# 1_Sheet_1.net
KiCad netlist of a schematic drawn in Altium Designer
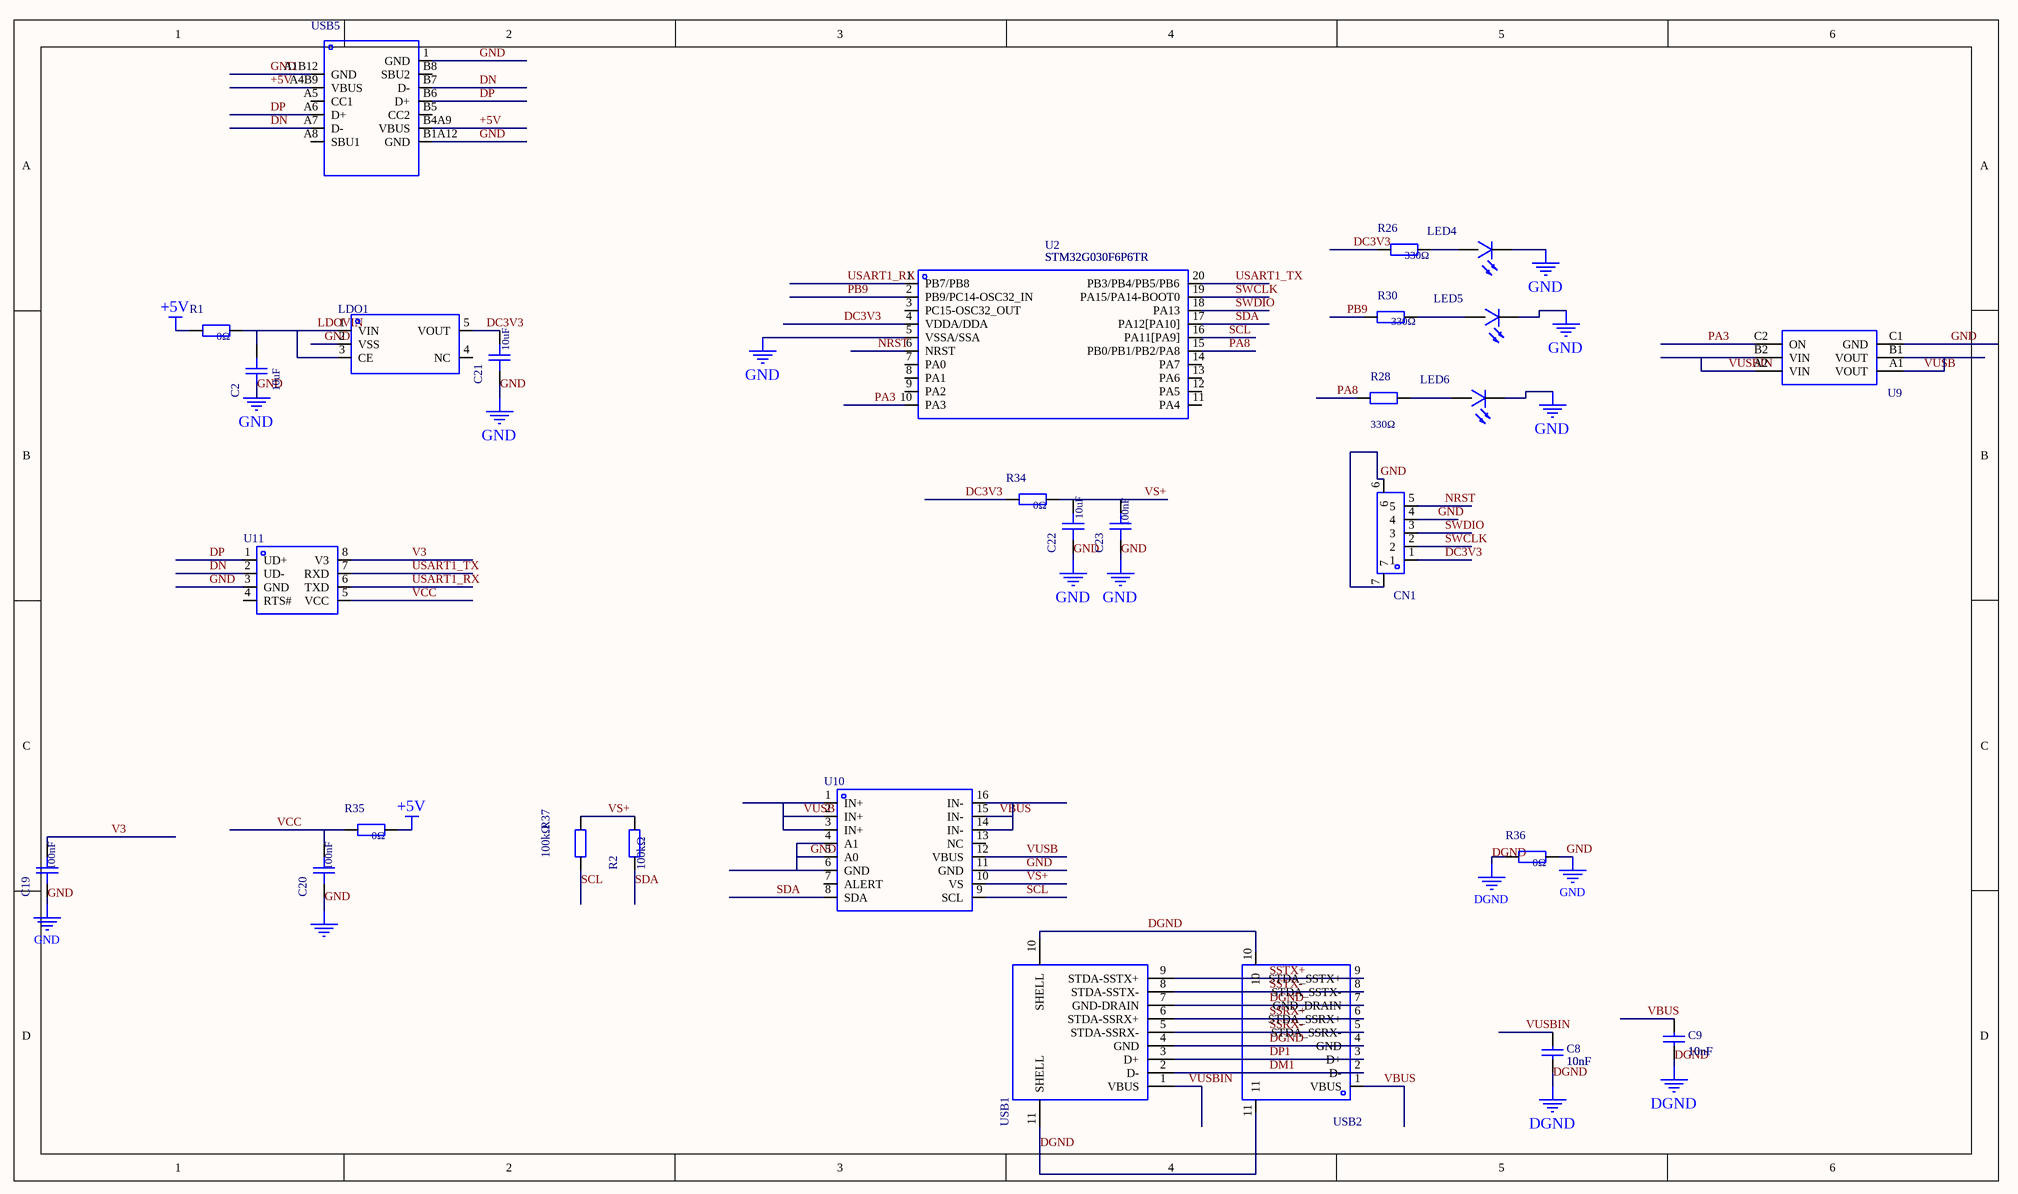
[diagram p0: 1_Sheet_1.schdoc]

(export (version "E")
  (design (tool "Eeschema 10.0.6"))
  (components
    (comp (ref "C2")
      (value "~")
      (fields
        (field (name "MANUFACTURER") "SAMSUNG(三星)")
        (field (name "MANUFACTURER PART") "CL10A106MA8NRNC")
        (field (name "TOLERANCE") "±20%")
        (field (name "CAPACITANCE") "10uF")
      )
      (libsource (lib "altium-import") (part "root_1_CL10A106MA8NRNC_"))
    )
    (comp (ref "C8")
      (value "10nF")
      (fields
        (field (name "NAME") "10nF")
        (field (name "MANUFACTURER PART") "CL05B103KB5NNNC")
        (field (name "MANUFACTURER") "SAMSUNG")
      )
      (libsource (lib "altium-import") (part "root_1_CL05B103KB5NNNC_"))
    )
    (comp (ref "C9")
      (value "10nF")
      (fields
        (field (name "NAME") "10nF")
        (field (name "MANUFACTURER PART") "CL05B103KB5NNNC")
        (field (name "MANUFACTURER") "SAMSUNG")
      )
      (libsource (lib "altium-import") (part "root_1_CL05B103KB5NNNC_"))
    )
    (comp (ref "C19")
      (value "~")
      (fields
        (field (name "MANUFACTURER") "YAGEO(国巨)")
        (field (name "MANUFACTURER PART") "CC0402KRX7R7BB104")
        (field (name "CAPACITANCE") "100nF")
        (field (name "TOLERANCE") "±10%")
      )
      (libsource (lib "altium-import") (part "root_1_CC0402KRX7R7BB104_"))
    )
    (comp (ref "C20")
      (value "~")
      (fields
        (field (name "MANUFACTURER") "YAGEO(国巨)")
        (field (name "MANUFACTURER PART") "CC0402KRX7R7BB104")
        (field (name "CAPACITANCE") "100nF")
        (field (name "TOLERANCE") "±10%")
      )
      (libsource (lib "altium-import") (part "root_1_CC0402KRX7R7BB104_"))
    )
    (comp (ref "C21")
      (value "~")
      (fields
        (field (name "MANUFACTURER") "SAMSUNG(三星)")
        (field (name "MANUFACTURER PART") "CL10A106MA8NRNC")
        (field (name "TOLERANCE") "±20%")
        (field (name "CAPACITANCE") "10uF")
      )
      (libsource (lib "altium-import") (part "root_1_CL10A106MA8NRNC_"))
    )
    (comp (ref "C22")
      (value "~")
      (fields
        (field (name "MANUFACTURER") "SAMSUNG(三星)")
        (field (name "MANUFACTURER PART") "CL10A106MA8NRNC")
        (field (name "TOLERANCE") "±20%")
        (field (name "CAPACITANCE") "10uF")
      )
      (libsource (lib "altium-import") (part "root_1_CL10A106MA8NRNC_"))
    )
    (comp (ref "C23")
      (value "~")
      (fields
        (field (name "MANUFACTURER") "YAGEO(国巨)")
        (field (name "MANUFACTURER PART") "CC0402KRX7R7BB104")
        (field (name "CAPACITANCE") "100nF")
        (field (name "TOLERANCE") "±10%")
      )
      (libsource (lib "altium-import") (part "root_1_CC0402KRX7R7BB104_"))
    )
    (comp (ref "CN1")
      (value "~")
      (fields (field (name "MANUFACTURER") "SHOU HAN(首韩)") (field (name "MANUFACTURER PART") "2.54-5P LT"))
      (libsource (lib "altium-import") (part "root_2_2.54-5P LT_"))
    )
    (comp (ref "LDO1")
      (value "~")
      (description "最大输入电压:6V;压降(max):260mV @ 200mA(typ);输出电压(可调):-;静态电流(Iq):-;输出类型:固定;输出电压(固定):3.3V;")
      (fields
        (field (name "MANUFACTURER") "MICRONE(南京微盟)")
        (field (name "MANUFACTURER PART") "ME6211C33M5G-N")
      )
      (libsource (lib "altium-import") (part "root_0_ME6211C33M5G-N_"))
    )
    (comp (ref "LED4")
      (value "~")
      (description "照明颜色:红色;")
      (fields
        (field (name "MANUFACTURER") "EVERLIGHT(台湾亿光)")
        (field (name "MANUFACTURER PART") "16-213/SDRC/S530-A3/TR8")
      )
      (libsource (lib "altium-import") (part "root_2_16-213/SDRC/S530-A3/TR8_"))
    )
    (comp (ref "LED5")
      (value "~")
      (description "照明颜色:红色;")
      (fields
        (field (name "MANUFACTURER") "EVERLIGHT(台湾亿光)")
        (field (name "MANUFACTURER PART") "16-213/SDRC/S530-A3/TR8")
      )
      (libsource (lib "altium-import") (part "root_2_16-213/SDRC/S530-A3/TR8_"))
    )
    (comp (ref "LED6")
      (value "~")
      (description "照明颜色:红色;")
      (fields
        (field (name "MANUFACTURER") "EVERLIGHT(台湾亿光)")
        (field (name "MANUFACTURER PART") "16-213/SDRC/S530-A3/TR8")
      )
      (libsource (lib "altium-import") (part "root_2_16-213/SDRC/S530-A3/TR8_"))
    )
    (comp (ref "R1")
      (value "~")
      (fields
        (field (name "MANUFACTURER") "YAGEO(国巨)")
        (field (name "MANUFACTURER PART") "RC0402FR-070RL")
        (field (name "TOLERANCE") "±1%")
        (field (name "RESISTANCE") "0Ω")
      )
      (libsource (lib "altium-import") (part "root_0_RC0402FR-070RL_"))
    )
    (comp (ref "R2")
      (value "100kΩ")
      (fields
        (field (name "MANUFACTURER") "FH(风华)")
        (field (name "MANUFACTURER PART") "RC-02W104JT")
        (field (name "TOLERANCE") "±5%")
      )
      (libsource (lib "altium-import") (part "root_1_RC-02W104JT_"))
    )
    (comp (ref "R26")
      (value "~")
      (fields
        (field (name "MANUFACTURER") "UNI-ROYAL(厚声)")
        (field (name "MANUFACTURER PART") "0402WGF3300TCE")
        (field (name "RESISTANCE") "330Ω")
        (field (name "TOLERANCE") "±1%")
      )
      (libsource (lib "altium-import") (part "root_0_0402WGF3300TCE_"))
    )
    (comp (ref "R28")
      (value "~")
      (fields
        (field (name "MANUFACTURER") "UNI-ROYAL(厚声)")
        (field (name "MANUFACTURER PART") "0402WGF3300TCE")
        (field (name "RESISTANCE") "330Ω")
        (field (name "TOLERANCE") "±1%")
      )
      (libsource (lib "altium-import") (part "root_0_0402WGF3300TCE_"))
    )
    (comp (ref "R30")
      (value "~")
      (fields
        (field (name "MANUFACTURER") "UNI-ROYAL(厚声)")
        (field (name "MANUFACTURER PART") "0402WGF3300TCE")
        (field (name "RESISTANCE") "330Ω")
        (field (name "TOLERANCE") "±1%")
      )
      (libsource (lib "altium-import") (part "root_0_0402WGF3300TCE_"))
    )
    (comp (ref "R34")
      (value "~")
      (fields
        (field (name "MANUFACTURER") "YAGEO(国巨)")
        (field (name "MANUFACTURER PART") "RC0402FR-070RL")
        (field (name "TOLERANCE") "±1%")
        (field (name "RESISTANCE") "0Ω")
      )
      (libsource (lib "altium-import") (part "root_0_RC0402FR-070RL_"))
    )
    (comp (ref "R35")
      (value "~")
      (fields
        (field (name "MANUFACTURER") "YAGEO(国巨)")
        (field (name "MANUFACTURER PART") "RC0402FR-070RL")
        (field (name "TOLERANCE") "±1%")
        (field (name "RESISTANCE") "0Ω")
      )
      (libsource (lib "altium-import") (part "root_0_RC0402FR-070RL_"))
    )
    (comp (ref "R36")
      (value "~")
      (fields
        (field (name "MANUFACTURER") "YAGEO(国巨)")
        (field (name "MANUFACTURER PART") "RC0402FR-070RL")
        (field (name "TOLERANCE") "±1%")
        (field (name "RESISTANCE") "0Ω")
      )
      (libsource (lib "altium-import") (part "root_0_RC0402FR-070RL_"))
    )
    (comp (ref "R37")
      (value "100kΩ")
      (fields
        (field (name "MANUFACTURER") "FH(风华)")
        (field (name "MANUFACTURER PART") "RC-02W104JT")
        (field (name "TOLERANCE") "±5%")
      )
      (libsource (lib "altium-import") (part "root_1_RC-02W104JT_"))
    )
    (comp (ref "U2")
      (value "STM32G030F6P6TR")
      (fields (field (name "NAME") "STM32G030F6P6TR") (field (name "MANUFACTURER") "STMicroelectronics"))
      (libsource (lib "altium-import") (part "root_0_STM32G030F6P6TR_"))
    )
    (comp (ref "U9")
      (value "~")
      (description "TPS22964C 具有控制启动和快速输出放电的小型、超低导通电阻负载开关")
      (fields (field (name "MANUFACTURER") "TI(德州仪器)") (field (name "MANUFACTURER PART") "TPS22964CYZPR"))
      (libsource (lib "altium-import") (part "root_2_TPS22964CYZPR_"))
    )
    (comp (ref "U10")
      (value "~")
      (description "INA260 具有集成 2mΩ 并联电阻的高/低侧数字电流/功率监视器")
      (fields (field (name "MANUFACTURER") "TI(德州仪器)") (field (name "MANUFACTURER PART") "INA260AIPW"))
      (libsource (lib "altium-import") (part "root_0_INA260AIPW_"))
    )
    (comp (ref "U11")
      (value "~")
      (fields (field (name "MANUFACTURER") "WCH(南京沁恒)") (field (name "MANUFACTURER PART") "CH340N"))
      (libsource (lib "altium-import") (part "root_0_CH340N_"))
    )
    (comp (ref "USB1")
      (value "~")
      (description "公母:公头;连接器类型:USB - Type A;触点数量:9;标准:USB 3.0;")
      (fields (field (name "MANUFACTURER") "精拓金") (field (name "MANUFACTURER PART") "917-P81A205CS60202"))
      (libsource (lib "altium-import") (part "root_1_917-P81A205CS60202_"))
    )
    (comp (ref "USB2")
      (value "~")
      (description "公母:母座;连接器类型:USB - Type A;触点数量:5;标准:USB 3.1;")
      (fields
        (field (name "MANUFACTURER") "XKB Connectivity(中国星坤)")
        (field (name "MANUFACTURER PART") "U231-091N-4BLRA00-S-1")
      )
      (libsource (lib "altium-import") (part "root_2_U231-091N-4BLRA00-S-1_"))
    )
    (comp (ref "USB5")
      (value "~")
      (description "连接器类型:-;公母:-;触点数量:-;标准:-;")
      (fields (field (name "MANUFACTURER") "韩国韩荣") (field (name "MANUFACTURER PART") "TYPE-C-31-M-09"))
      (libsource (lib "altium-import") (part "root_0_TYPE-C-31-M-09_"))
    )
  )
  (nets
    (net (code "1") (name "+5V") (class "Default")
      (node (ref "R1") (pin "1") (pinfunction "1_1") (pintype "passive"))
      (node (ref "R35") (pin "2") (pinfunction "2_2") (pintype "passive"))
      (node (ref "USB5") (pin "A4B9") (pinfunction "VBUS_A4B9") (pintype "passive"))
      (node (ref "USB5") (pin "B4A9") (pinfunction "VBUS_B4A9") (pintype "passive"))
    )
    (net (code "2") (name "/DC3V3") (class "Default")
      (node (ref "C21") (pin "2") (pinfunction "2_2") (pintype "passive"))
      (node (ref "CN1") (pin "1") (pinfunction "1_1") (pintype "passive"))
      (node (ref "LDO1") (pin "5") (pinfunction "VOUT_5") (pintype "passive"))
      (node (ref "R26") (pin "1") (pinfunction "1_1") (pintype "passive"))
      (node (ref "R34") (pin "1") (pinfunction "1_1") (pintype "passive"))
      (node (ref "U2") (pin "4") (pinfunction "VDDA/DDA_4") (pintype "passive"))
    )
    (net (code "3") (name "/DM1") (class "Default")
      (node (ref "USB1") (pin "2") (pinfunction "D-_2") (pintype "passive"))
      (node (ref "USB2") (pin "2") (pinfunction "D-_2") (pintype "passive"))
    )
    (net (code "4") (name "/DN") (class "Default")
      (node (ref "U11") (pin "2") (pinfunction "UD-_2") (pintype "passive"))
      (node (ref "USB5") (pin "A7") (pinfunction "D-_A7") (pintype "passive"))
      (node (ref "USB5") (pin "B7") (pinfunction "D-_B7") (pintype "passive"))
    )
    (net (code "5") (name "/DP") (class "Default")
      (node (ref "U11") (pin "1") (pinfunction "UD+_1") (pintype "passive"))
      (node (ref "USB5") (pin "A6") (pinfunction "D+_A6") (pintype "passive"))
      (node (ref "USB5") (pin "B6") (pinfunction "D+_B6") (pintype "passive"))
    )
    (net (code "6") (name "/DP1") (class "Default")
      (node (ref "USB1") (pin "3") (pinfunction "D+_3") (pintype "passive"))
      (node (ref "USB2") (pin "3") (pinfunction "D+_3") (pintype "passive"))
    )
    (net (code "7") (name "/LDOVIN") (class "Default")
      (node (ref "C2") (pin "2") (pinfunction "2_2") (pintype "passive"))
      (node (ref "LDO1") (pin "1") (pinfunction "VIN_1") (pintype "passive"))
      (node (ref "LDO1") (pin "3") (pinfunction "CE_3") (pintype "passive"))
      (node (ref "R1") (pin "2") (pinfunction "2_2") (pintype "passive"))
    )
    (net (code "8") (name "/NRST") (class "Default")
      (node (ref "CN1") (pin "5") (pinfunction "5_5") (pintype "passive"))
      (node (ref "U2") (pin "6") (pinfunction "NRST_6") (pintype "passive"))
    )
    (net (code "9") (name "/PA3") (class "Default")
      (node (ref "U2") (pin "10") (pinfunction "PA3_10") (pintype "passive"))
      (node (ref "U9") (pin "C2") (pinfunction "ON_C2") (pintype "passive"))
    )
    (net (code "10") (name "/PA8") (class "Default")
      (node (ref "R28") (pin "1") (pinfunction "1_1") (pintype "passive"))
      (node (ref "U2") (pin "15") (pinfunction "PB0/PB1/PB2/PA8_15") (pintype "passive"))
    )
    (net (code "11") (name "/PB9") (class "Default")
      (node (ref "R30") (pin "1") (pinfunction "1_1") (pintype "passive"))
      (node (ref "U2") (pin "2") (pinfunction "PB9/PC14-OSC32_IN_2") (pintype "passive"))
    )
    (net (code "12") (name "/SCL") (class "Default")
      (node (ref "R37") (pin "1") (pinfunction "1_1") (pintype "passive"))
      (node (ref "U10") (pin "9") (pinfunction "SCL_9") (pintype "passive"))
      (node (ref "U2") (pin "16") (pinfunction "PA11[PA9]_16") (pintype "passive"))
    )
    (net (code "13") (name "/SDA") (class "Default")
      (node (ref "R2") (pin "1") (pinfunction "1_1") (pintype "passive"))
      (node (ref "U10") (pin "8") (pinfunction "SDA_8") (pintype "passive"))
      (node (ref "U2") (pin "17") (pinfunction "PA12[PA10]_17") (pintype "passive"))
    )
    (net (code "14") (name "/SSRX+") (class "Default")
      (node (ref "USB1") (pin "6") (pinfunction "STDA-SSRX+_6") (pintype "passive"))
      (node (ref "USB2") (pin "6") (pinfunction "STDA_SSRX+_6") (pintype "passive"))
    )
    (net (code "15") (name "/SSRX-") (class "Default")
      (node (ref "USB1") (pin "5") (pinfunction "STDA-SSRX-_5") (pintype "passive"))
      (node (ref "USB2") (pin "5") (pinfunction "STDA_SSRX-_5") (pintype "passive"))
    )
    (net (code "16") (name "/SSTX+") (class "Default")
      (node (ref "USB1") (pin "9") (pinfunction "STDA-SSTX+_9") (pintype "passive"))
      (node (ref "USB2") (pin "9") (pinfunction "STDA_SSTX+_9") (pintype "passive"))
    )
    (net (code "17") (name "/SSTX-") (class "Default")
      (node (ref "USB1") (pin "8") (pinfunction "STDA-SSTX-_8") (pintype "passive"))
      (node (ref "USB2") (pin "8") (pinfunction "STDA_SSTX-_8") (pintype "passive"))
    )
    (net (code "18") (name "/SWCLK") (class "Default")
      (node (ref "CN1") (pin "2") (pinfunction "2_2") (pintype "passive"))
      (node (ref "U2") (pin "19") (pinfunction "PA15/PA14-BOOT0_19") (pintype "passive"))
    )
    (net (code "19") (name "/SWDIO") (class "Default")
      (node (ref "CN1") (pin "3") (pinfunction "3_3") (pintype "passive"))
      (node (ref "U2") (pin "18") (pinfunction "PA13_18") (pintype "passive"))
    )
    (net (code "20") (name "/USART1_RX") (class "Default")
      (node (ref "U11") (pin "6") (pinfunction "TXD_6") (pintype "passive"))
      (node (ref "U2") (pin "1") (pinfunction "PB7/PB8_1") (pintype "passive"))
    )
    (net (code "21") (name "/USART1_TX") (class "Default")
      (node (ref "U11") (pin "7") (pinfunction "RXD_7") (pintype "passive"))
      (node (ref "U2") (pin "20") (pinfunction "PB3/PB4/PB5/PB6_20") (pintype "passive"))
    )
    (net (code "22") (name "/V3") (class "Default")
      (node (ref "C19") (pin "2") (pinfunction "2_2") (pintype "passive"))
      (node (ref "U11") (pin "8") (pinfunction "V3_8") (pintype "passive"))
    )
    (net (code "23") (name "/VBUS") (class "Default")
      (node (ref "C9") (pin "2") (pinfunction "2_2") (pintype "passive"))
      (node (ref "U10") (pin "14") (pinfunction "IN-_14") (pintype "passive"))
      (node (ref "U10") (pin "15") (pinfunction "IN-_15") (pintype "passive"))
      (node (ref "U10") (pin "16") (pinfunction "IN-_16") (pintype "passive"))
      (node (ref "USB2") (pin "1") (pinfunction "VBUS_1") (pintype "passive"))
    )
    (net (code "24") (name "/VCC") (class "Default")
      (node (ref "C20") (pin "2") (pinfunction "2_2") (pintype "passive"))
      (node (ref "R35") (pin "1") (pinfunction "1_1") (pintype "passive"))
      (node (ref "U11") (pin "5") (pinfunction "VCC_5") (pintype "passive"))
    )
    (net (code "25") (name "/VS+") (class "Default")
      (node (ref "C22") (pin "2") (pinfunction "2_2") (pintype "passive"))
      (node (ref "C23") (pin "2") (pinfunction "2_2") (pintype "passive"))
      (node (ref "R2") (pin "2") (pinfunction "2_2") (pintype "passive"))
      (node (ref "R34") (pin "2") (pinfunction "2_2") (pintype "passive"))
      (node (ref "R37") (pin "2") (pinfunction "2_2") (pintype "passive"))
      (node (ref "U10") (pin "10") (pinfunction "VS_10") (pintype "passive"))
    )
    (net (code "26") (name "/VUSB") (class "Default")
      (node (ref "U10") (pin "1") (pinfunction "IN+_1") (pintype "passive"))
      (node (ref "U10") (pin "12") (pinfunction "VBUS_12") (pintype "passive"))
      (node (ref "U10") (pin "2") (pinfunction "IN+_2") (pintype "passive"))
      (node (ref "U10") (pin "3") (pinfunction "IN+_3") (pintype "passive"))
      (node (ref "U9") (pin "A1") (pinfunction "VOUT_A1") (pintype "passive"))
      (node (ref "U9") (pin "B1") (pinfunction "VOUT_B1") (pintype "passive"))
    )
    (net (code "27") (name "/VUSBIN") (class "Default")
      (node (ref "C8") (pin "2") (pinfunction "2_2") (pintype "passive"))
      (node (ref "U9") (pin "A2") (pinfunction "VIN_A2") (pintype "passive"))
      (node (ref "U9") (pin "B2") (pinfunction "VIN_B2") (pintype "passive"))
      (node (ref "USB1") (pin "1") (pinfunction "VBUS_1") (pintype "passive"))
    )
    (net (code "28") (name "DGND") (class "Default")
      (node (ref "C8") (pin "1") (pinfunction "1_1") (pintype "passive"))
      (node (ref "C9") (pin "1") (pinfunction "1_1") (pintype "passive"))
      (node (ref "R36") (pin "1") (pinfunction "1_1") (pintype "passive"))
      (node (ref "USB1") (pin "10") (pinfunction "SHELL_10") (pintype "passive"))
      (node (ref "USB1") (pin "11") (pinfunction "SHELL_11") (pintype "passive"))
      (node (ref "USB1") (pin "4") (pinfunction "GND_4") (pintype "passive"))
      (node (ref "USB1") (pin "7") (pinfunction "GND-DRAIN_7") (pintype "passive"))
      (node (ref "USB2") (pin "10") (pinfunction "10_10") (pintype "passive"))
      (node (ref "USB2") (pin "11") (pinfunction "11_11") (pintype "passive"))
      (node (ref "USB2") (pin "4") (pinfunction "GND_4") (pintype "passive"))
      (node (ref "USB2") (pin "7") (pinfunction "GND_DRAIN_7") (pintype "passive"))
    )
    (net (code "29") (name "GND") (class "Default")
      (node (ref "C19") (pin "1") (pinfunction "1_1") (pintype "passive"))
      (node (ref "C2") (pin "1") (pinfunction "1_1") (pintype "passive"))
      (node (ref "C20") (pin "1") (pinfunction "1_1") (pintype "passive"))
      (node (ref "C21") (pin "1") (pinfunction "1_1") (pintype "passive"))
      (node (ref "C22") (pin "1") (pinfunction "1_1") (pintype "passive"))
      (node (ref "C23") (pin "1") (pinfunction "1_1") (pintype "passive"))
      (node (ref "CN1") (pin "4") (pinfunction "4_4") (pintype "passive"))
      (node (ref "CN1") (pin "6") (pinfunction "6_6") (pintype "passive"))
      (node (ref "CN1") (pin "7") (pinfunction "7_7") (pintype "passive"))
      (node (ref "LDO1") (pin "2") (pinfunction "VSS_2") (pintype "passive"))
      (node (ref "LED4") (pin "1") (pinfunction "-_1") (pintype "passive"))
      (node (ref "LED5") (pin "1") (pinfunction "-_1") (pintype "passive"))
      (node (ref "LED6") (pin "1") (pinfunction "-_1") (pintype "passive"))
      (node (ref "R36") (pin "2") (pinfunction "2_2") (pintype "passive"))
      (node (ref "U10") (pin "11") (pinfunction "GND_11") (pintype "passive"))
      (node (ref "U10") (pin "4") (pinfunction "A1_4") (pintype "passive"))
      (node (ref "U10") (pin "5") (pinfunction "A0_5") (pintype "passive"))
      (node (ref "U10") (pin "6") (pinfunction "GND_6") (pintype "passive"))
      (node (ref "U11") (pin "3") (pinfunction "GND_3") (pintype "passive"))
      (node (ref "U2") (pin "5") (pinfunction "VSSA/SSA_5") (pintype "passive"))
      (node (ref "U9") (pin "C1") (pinfunction "GND_C1") (pintype "passive"))
      (node (ref "USB5") (pin "1") (pinfunction "GND_1") (pintype "passive"))
      (node (ref "USB5") (pin "A1B12") (pinfunction "GND_A1B12") (pintype "passive"))
      (node (ref "USB5") (pin "B1A12") (pinfunction "GND_B1A12") (pintype "passive"))
    )
    (net (code "30") (name "Net-(LED4-+)") (class "Default")
      (node (ref "LED4") (pin "2") (pinfunction "+_2") (pintype "passive"))
      (node (ref "R26") (pin "2") (pinfunction "2_2") (pintype "passive"))
    )
    (net (code "31") (name "Net-(LED5-+)") (class "Default")
      (node (ref "LED5") (pin "2") (pinfunction "+_2") (pintype "passive"))
      (node (ref "R30") (pin "2") (pinfunction "2_2") (pintype "passive"))
    )
    (net (code "32") (name "Net-(LED6-+)") (class "Default")
      (node (ref "LED6") (pin "2") (pinfunction "+_2") (pintype "passive"))
      (node (ref "R28") (pin "2") (pinfunction "2_2") (pintype "passive"))
    )
    (net (code "33") (name "unconnected-(LDO1-NC-Pad4)") (class "Default")
      (node (ref "LDO1") (pin "4") (pinfunction "NC_4") (pintype "passive"))
    )
    (net (code "34") (name "unconnected-(U2-PA0-Pad7)") (class "Default")
      (node (ref "U2") (pin "7") (pinfunction "PA0_7") (pintype "passive"))
    )
    (net (code "35") (name "unconnected-(U2-PA1-Pad8)") (class "Default")
      (node (ref "U2") (pin "8") (pinfunction "PA1_8") (pintype "passive"))
    )
    (net (code "36") (name "unconnected-(U2-PA2-Pad9)") (class "Default")
      (node (ref "U2") (pin "9") (pinfunction "PA2_9") (pintype "passive"))
    )
    (net (code "37") (name "unconnected-(U2-PA4-Pad11)") (class "Default")
      (node (ref "U2") (pin "11") (pinfunction "PA4_11") (pintype "passive"))
    )
    (net (code "38") (name "unconnected-(U2-PA5-Pad12)") (class "Default")
      (node (ref "U2") (pin "12") (pinfunction "PA5_12") (pintype "passive"))
    )
    (net (code "39") (name "unconnected-(U2-PA6-Pad13)") (class "Default")
      (node (ref "U2") (pin "13") (pinfunction "PA6_13") (pintype "passive"))
    )
    (net (code "40") (name "unconnected-(U2-PA7-Pad14)") (class "Default")
      (node (ref "U2") (pin "14") (pinfunction "PA7_14") (pintype "passive"))
    )
    (net (code "41") (name "unconnected-(U2-PC15-OSC32_OUT-Pad3)") (class "Default")
      (node (ref "U2") (pin "3") (pinfunction "PC15-OSC32_OUT_3") (pintype "passive"))
    )
    (net (code "42") (name "unconnected-(U10-ALERT-Pad7)") (class "Default")
      (node (ref "U10") (pin "7") (pinfunction "ALERT_7") (pintype "passive"))
    )
    (net (code "43") (name "unconnected-(U10-NC-Pad13)") (class "Default")
      (node (ref "U10") (pin "13") (pinfunction "NC_13") (pintype "passive"))
    )
    (net (code "44") (name "unconnected-(U11-RTS#-Pad4)") (class "Default")
      (node (ref "U11") (pin "4") (pinfunction "RTS#_4") (pintype "passive"))
    )
    (net (code "45") (name "unconnected-(USB5-CC1-PadA5)") (class "Default")
      (node (ref "USB5") (pin "A5") (pinfunction "CC1_A5") (pintype "passive"))
    )
    (net (code "46") (name "unconnected-(USB5-CC2-PadB5)") (class "Default")
      (node (ref "USB5") (pin "B5") (pinfunction "CC2_B5") (pintype "passive"))
    )
    (net (code "47") (name "unconnected-(USB5-SBU1-PadA8)") (class "Default")
      (node (ref "USB5") (pin "A8") (pinfunction "SBU1_A8") (pintype "passive"))
    )
    (net (code "48") (name "unconnected-(USB5-SBU2-PadB8)") (class "Default")
      (node (ref "USB5") (pin "B8") (pinfunction "SBU2_B8") (pintype "passive"))
    )
  )
)
